# MAX-M8Q_GPS_FeatherWing.net
KiCad netlist of a schematic drawn in EAGLE
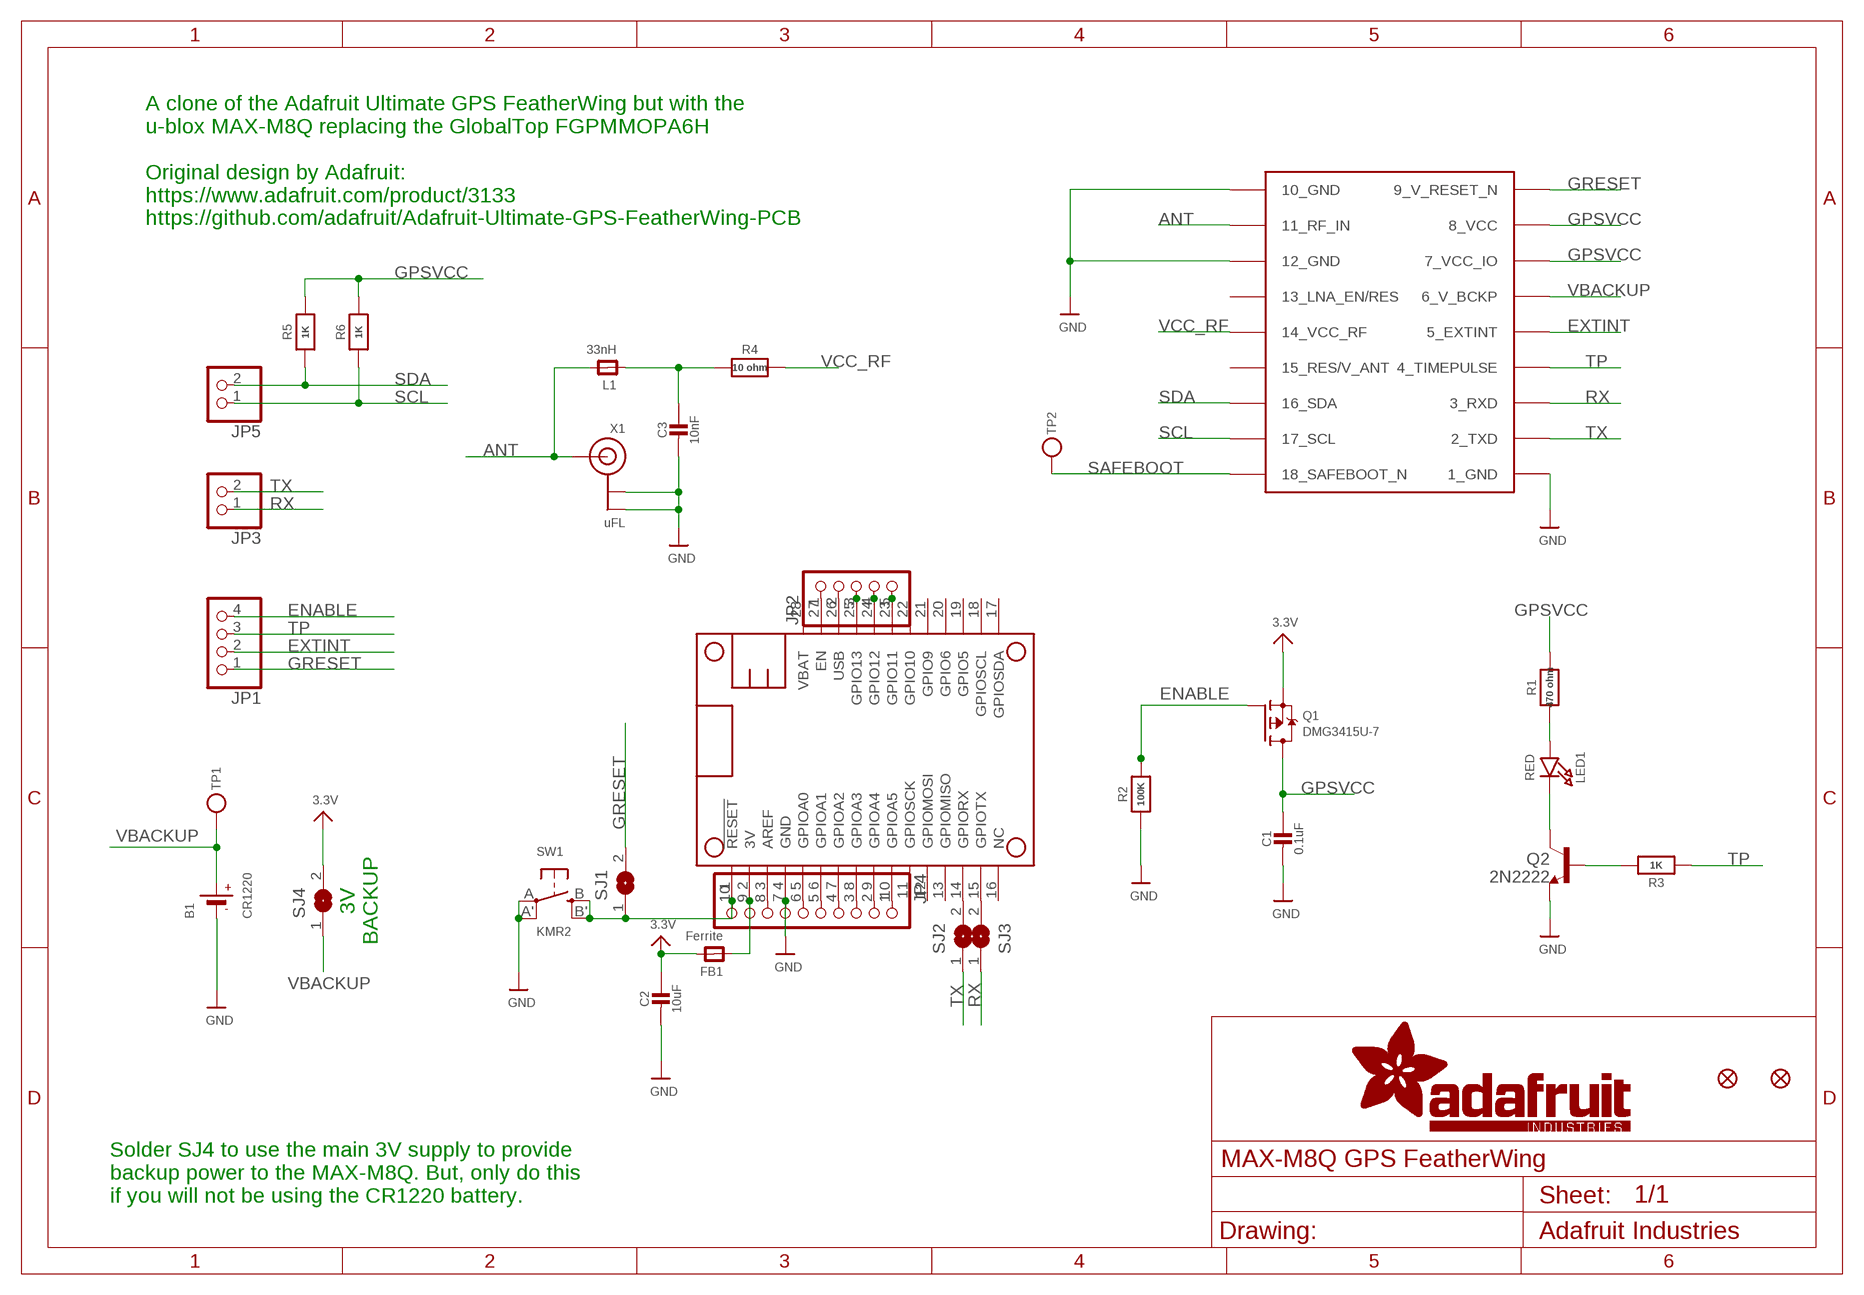
[diagram p0: schematic, sheet 1]

(export (version "E")
  (design (tool "Eeschema 10.0.6"))
  (components
    (comp (ref "B1")
      (value "CR1220")
      (footprint "eagle-import:CR1220-2")
      (libsource (lib "eagle-import") (part "BATTERYCR1220_2"))
    )
    (comp (ref "C1")
      (value "0.1uF")
      (footprint "eagle-import:0805-NO")
      (libsource (lib "eagle-import") (part "CAP_CERAMIC0805-NOOUTLINE"))
    )
    (comp (ref "C2")
      (value "10uF")
      (footprint "eagle-import:0805-NO")
      (libsource (lib "eagle-import") (part "CAP_CERAMIC0805-NOOUTLINE"))
    )
    (comp (ref "C3")
      (value "10nF")
      (footprint "eagle-import:0805-NO")
      (libsource (lib "eagle-import") (part "CAP_CERAMIC0805-NOOUTLINE"))
    )
    (comp (ref "FB1")
      (value "Ferrite")
      (footprint "eagle-import:0805-NO")
      (libsource (lib "eagle-import") (part "FERRITE-0805NO"))
    )
    (comp (ref "FID1")
      (value "FIDUCIAL\"\"")
      (footprint "eagle-import:FIDUCIAL_1MM")
      (libsource (lib "eagle-import") (part "FIDUCIAL{dblquote}{dblquote}"))
    )
    (comp (ref "FID2")
      (value "FIDUCIAL\"\"")
      (footprint "eagle-import:FIDUCIAL_1MM")
      (libsource (lib "eagle-import") (part "FIDUCIAL{dblquote}{dblquote}"))
    )
    (comp (ref "JP1")
      (value "HEADER-1X4ROUND")
      (footprint "eagle-import:1X04_ROUND")
      (libsource (lib "eagle-import") (part "HEADER-1X4ROUND"))
    )
    (comp (ref "JP2")
      (value "HEADER-1X570MIL")
      (footprint "eagle-import:1X05_ROUND_70")
      (libsource (lib "eagle-import") (part "HEADER-1X570MIL"))
    )
    (comp (ref "JP3")
      (value "HEADER-1X2ROUND")
      (footprint "eagle-import:1X02_ROUND")
      (libsource (lib "eagle-import") (part "HEADER-1X2ROUND"))
    )
    (comp (ref "JP4")
      (value "HEADER-1X10ROUND")
      (footprint "eagle-import:1X10_ROUND")
      (libsource (lib "eagle-import") (part "HEADER-1X10ROUND"))
    )
    (comp (ref "JP5")
      (value "HEADER-1X2ROUND")
      (footprint "eagle-import:1X02_ROUND")
      (libsource (lib "eagle-import") (part "HEADER-1X2ROUND"))
    )
    (comp (ref "L1")
      (value "33nH")
      (footprint "eagle-import:0805-NO")
      (libsource (lib "eagle-import") (part "FERRITE-0805NO"))
    )
    (comp (ref "LED1")
      (value "RED")
      (footprint "eagle-import:CHIPLED_0805_NOOUTLINE")
      (libsource (lib "eagle-import") (part "LED0805_NOOUTLINE"))
    )
    (comp (ref "MS1")
      (value "FEATHERWING")
      (footprint "eagle-import:FEATHERWING")
      (libsource (lib "eagle-import") (part "FEATHERWING"))
    )
    (comp (ref "Q1")
      (value "DMG3415U-7")
      (footprint "eagle-import:SOT23-WIDE")
      (libsource (lib "eagle-import") (part "MOSFET-PWIDE"))
    )
    (comp (ref "Q2")
      (value "2N2222")
      (footprint "eagle-import:SOT23-BEC")
      (libsource (lib "eagle-import") (part "-NPN-SOT23-BECMMBT2222ALT1"))
    )
    (comp (ref "R1")
      (value "470 ohm")
      (footprint "eagle-import:0805-NO")
      (libsource (lib "eagle-import") (part "RESISTOR0805_NOOUTLINE"))
    )
    (comp (ref "R2")
      (value "100K")
      (footprint "eagle-import:0805-NO")
      (libsource (lib "eagle-import") (part "RESISTOR0805_NOOUTLINE"))
    )
    (comp (ref "R3")
      (value "1K")
      (footprint "eagle-import:0805-NO")
      (libsource (lib "eagle-import") (part "RESISTOR0805_NOOUTLINE"))
    )
    (comp (ref "R4")
      (value "10 ohm")
      (footprint "eagle-import:0805-NO")
      (libsource (lib "eagle-import") (part "RESISTOR0805_NOOUTLINE"))
    )
    (comp (ref "R5")
      (value "1K")
      (footprint "eagle-import:0805-NO")
      (libsource (lib "eagle-import") (part "RESISTOR0805_NOOUTLINE"))
    )
    (comp (ref "R6")
      (value "1K")
      (footprint "eagle-import:0805-NO")
      (libsource (lib "eagle-import") (part "RESISTOR0805_NOOUTLINE"))
    )
    (comp (ref "SJ1")
      (value "SOLDERJUMPER")
      (footprint "eagle-import:SOLDERJUMPER_ARROW_NOPASTE")
      (libsource (lib "eagle-import") (part "SOLDERJUMPER"))
    )
    (comp (ref "SJ2")
      (value "SOLDERJUMPERCLOSED")
      (footprint "eagle-import:SOLDERJUMPER_CLOSEDWIRE")
      (libsource (lib "eagle-import") (part "SOLDERJUMPERCLOSED"))
    )
    (comp (ref "SJ3")
      (value "SOLDERJUMPERCLOSED")
      (footprint "eagle-import:SOLDERJUMPER_CLOSEDWIRE")
      (libsource (lib "eagle-import") (part "SOLDERJUMPERCLOSED"))
    )
    (comp (ref "SJ4")
      (value "SOLDERJUMPER")
      (footprint "eagle-import:SOLDERJUMPER_ARROW_NOPASTE")
      (libsource (lib "eagle-import") (part "SOLDERJUMPER"))
    )
    (comp (ref "SW1")
      (value "KMR2")
      (footprint "eagle-import:BTN_KMR2_4.6X2.8")
      (libsource (lib "eagle-import") (part "SWITCH_TACT_SMT4.6X2.8"))
    )
    (comp (ref "TP1")
      (value "TESTPOINTROUND1.5MM")
      (footprint "eagle-import:TESTPOINT_ROUND_1.5MM")
      (libsource (lib "eagle-import") (part "TESTPOINTROUND1.5MM"))
    )
    (comp (ref "TP2")
      (value "TESTPOINTROUND1.5MM")
      (footprint "eagle-import:TESTPOINT_ROUND_1.5MM")
      (libsource (lib "eagle-import") (part "TESTPOINTROUND1.5MM"))
    )
    (comp (ref "U1")
      (value "MAX-M8")
      (footprint "eagle-import:MAX-M8")
      (libsource (lib "eagle-import") (part "MAX-M8"))
    )
    (comp (ref "X1")
      (value "uFL")
      (footprint "eagle-import:U.FL")
      (libsource (lib "eagle-import") (part "ANTENNA_U.FL"))
    )
  )
  (nets
    (net (code "1") (name "/ANT") (class "Default")
      (node (ref "L1") (pin "2") (pinfunction "P$2_2") (pintype "passive"))
      (node (ref "U1") (pin "11_RF_IN") (pinfunction "11_RF_IN_11_RF_IN") (pintype "bidirectional"))
      (node (ref "X1") (pin "3") (pinfunction "SIGNAL_3") (pintype "passive"))
    )
    (net (code "2") (name "/ENABLE") (class "Default")
      (node (ref "JP1") (pin "4") (pinfunction "4_4") (pintype "passive"))
      (node (ref "Q1") (pin "1") (pinfunction "G_1") (pintype "passive"))
      (node (ref "R2") (pin "2") (pinfunction "2_2") (pintype "passive"))
    )
    (net (code "3") (name "/EXTINT") (class "Default")
      (node (ref "JP1") (pin "2") (pinfunction "2_2") (pintype "passive"))
      (node (ref "U1") (pin "5_EXTINT") (pinfunction "5_EXTINT_5_EXTINT") (pintype "bidirectional"))
    )
    (net (code "4") (name "/GPSVCC") (class "Default")
      (node (ref "C1") (pin "1") (pinfunction "1_1") (pintype "passive"))
      (node (ref "Q1") (pin "3") (pinfunction "D_3") (pintype "passive"))
      (node (ref "R1") (pin "2") (pinfunction "2_2") (pintype "passive"))
      (node (ref "R5") (pin "2") (pinfunction "2_2") (pintype "passive"))
      (node (ref "R6") (pin "2") (pinfunction "2_2") (pintype "passive"))
      (node (ref "U1") (pin "7_VCC_IO") (pinfunction "7_VCC_IO_7_VCC_IO") (pintype "power_in"))
      (node (ref "U1") (pin "8_VCC") (pinfunction "8_VCC_8_VCC") (pintype "power_in"))
    )
    (net (code "5") (name "/GRESET") (class "Default")
      (node (ref "JP1") (pin "1") (pinfunction "1_1") (pintype "passive"))
      (node (ref "SJ1") (pin "2") (pinfunction "2_2") (pintype "passive"))
      (node (ref "U1") (pin "9_RESET_N") (pinfunction "9_V_RESET_N_9_RESET_N") (pintype "power_in"))
    )
    (net (code "6") (name "/RX") (class "Default")
      (node (ref "JP3") (pin "1") (pinfunction "1_1") (pintype "passive"))
      (node (ref "SJ3") (pin "1") (pinfunction "1_1") (pintype "passive"))
      (node (ref "U1") (pin "3_RXD") (pinfunction "3_RXD_3_RXD") (pintype "bidirectional"))
    )
    (net (code "7") (name "/SAFEBOOT") (class "Default")
      (node (ref "TP2") (pin "P$1") (pinfunction "P$1_P$1") (pintype "bidirectional"))
      (node (ref "U1") (pin "18_SAFEBOOT_N") (pinfunction "18_SAFEBOOT_N_18_SAFEBOOT_N") (pintype "bidirectional"))
    )
    (net (code "8") (name "/SCL") (class "Default")
      (node (ref "JP5") (pin "1") (pinfunction "1_1") (pintype "passive"))
      (node (ref "R6") (pin "1") (pinfunction "1_1") (pintype "passive"))
      (node (ref "U1") (pin "17_SCL") (pinfunction "17_SCL_17_SCL") (pintype "bidirectional"))
    )
    (net (code "9") (name "/SDA") (class "Default")
      (node (ref "JP5") (pin "2") (pinfunction "2_2") (pintype "passive"))
      (node (ref "R5") (pin "1") (pinfunction "1_1") (pintype "passive"))
      (node (ref "U1") (pin "16_SDA") (pinfunction "16_SDA_16_SDA") (pintype "bidirectional"))
    )
    (net (code "10") (name "/TP") (class "Default")
      (node (ref "JP1") (pin "3") (pinfunction "3_3") (pintype "passive"))
      (node (ref "R3") (pin "1") (pinfunction "1_1") (pintype "passive"))
      (node (ref "U1") (pin "4_TIMEPULSE") (pinfunction "4_TIMEPULSE_4_TIMEPULSE") (pintype "bidirectional"))
    )
    (net (code "11") (name "/TX") (class "Default")
      (node (ref "JP3") (pin "2") (pinfunction "2_2") (pintype "passive"))
      (node (ref "SJ2") (pin "1") (pinfunction "1_1") (pintype "passive"))
      (node (ref "U1") (pin "2_TXD") (pinfunction "2_TXD_2_TXD") (pintype "bidirectional"))
    )
    (net (code "12") (name "/VBACKUP") (class "Default")
      (node (ref "B1") (pin "+") (pinfunction "+_+") (pintype "passive"))
      (node (ref "SJ4") (pin "1") (pinfunction "1_1") (pintype "passive"))
      (node (ref "TP1") (pin "P$1") (pinfunction "P$1_P$1") (pintype "bidirectional"))
      (node (ref "U1") (pin "6_V_BCKP") (pinfunction "6_V_BCKP_6_V_BCKP") (pintype "bidirectional"))
    )
    (net (code "13") (name "/VBAT") (class "Default")
      (node (ref "MS1") (pin "28") (pinfunction "VBAT_28") (pintype "power_in"))
    )
    (net (code "14") (name "/VCC_RF") (class "Default")
      (node (ref "R4") (pin "2") (pinfunction "2_2") (pintype "passive"))
      (node (ref "U1") (pin "14_VCC_RF") (pinfunction "14_VCC_RF_14_VCC_RF") (pintype "bidirectional"))
    )
    (net (code "15") (name "3.3V") (class "Default")
      (node (ref "C2") (pin "1") (pinfunction "1_1") (pintype "passive"))
      (node (ref "FB1") (pin "2") (pinfunction "P$2_2") (pintype "passive"))
      (node (ref "Q1") (pin "2") (pinfunction "S_2") (pintype "passive"))
      (node (ref "SJ4") (pin "2") (pinfunction "2_2") (pintype "passive"))
    )
    (net (code "16") (name "GND") (class "Default")
      (node (ref "B1") (pin "-") (pinfunction "-_-") (pintype "passive"))
      (node (ref "C1") (pin "2") (pinfunction "2_2") (pintype "passive"))
      (node (ref "C2") (pin "2") (pinfunction "2_2") (pintype "passive"))
      (node (ref "C3") (pin "2") (pinfunction "2_2") (pintype "passive"))
      (node (ref "JP4") (pin "7") (pinfunction "7_7") (pintype "passive"))
      (node (ref "MS1") (pin "4") (pinfunction "GND_4") (pintype "power_in"))
      (node (ref "Q2") (pin "E") (pinfunction "E_E") (pintype "passive"))
      (node (ref "R2") (pin "1") (pinfunction "1_1") (pintype "passive"))
      (node (ref "SW1") (pin "A") (pinfunction "P_A") (pintype "passive"))
      (node (ref "SW1") (pin "A'") (pinfunction "P1_A'") (pintype "passive"))
      (node (ref "U1") (pin "10_GND") (pinfunction "10_GND_10_GND") (pintype "power_in"))
      (node (ref "U1") (pin "12_GND") (pinfunction "12_GND_12_GND") (pintype "power_in"))
      (node (ref "U1") (pin "1_GND") (pinfunction "1_GND_1_GND") (pintype "power_in"))
      (node (ref "X1") (pin "1") (pinfunction "GND_1") (pintype "passive"))
      (node (ref "X1") (pin "2") (pinfunction "GND_2") (pintype "passive"))
    )
    (net (code "17") (name "Net-(FB1-P$1)") (class "Default")
      (node (ref "FB1") (pin "1") (pinfunction "P$1_1") (pintype "passive"))
      (node (ref "JP4") (pin "9") (pinfunction "9_9") (pintype "passive"))
      (node (ref "MS1") (pin "2") (pinfunction "3V_2") (pintype "power_in"))
    )
    (net (code "18") (name "Net-(L1-P$1)") (class "Default")
      (node (ref "C3") (pin "1") (pinfunction "1_1") (pintype "passive"))
      (node (ref "L1") (pin "1") (pinfunction "P$1_1") (pintype "passive"))
      (node (ref "R4") (pin "1") (pinfunction "1_1") (pintype "passive"))
    )
    (net (code "19") (name "Net-(LED1-PadA)") (class "Default")
      (node (ref "LED1") (pin "A") (pinfunction "A_A") (pintype "passive"))
      (node (ref "R1") (pin "1") (pinfunction "1_1") (pintype "passive"))
    )
    (net (code "20") (name "Net-(LED1-PadC)") (class "Default")
      (node (ref "LED1") (pin "C") (pinfunction "C_C") (pintype "passive"))
      (node (ref "Q2") (pin "C") (pinfunction "C_C") (pintype "passive"))
    )
    (net (code "21") (name "Net-(MS1-AREF)") (class "Default")
      (node (ref "JP4") (pin "8") (pinfunction "8_8") (pintype "passive"))
      (node (ref "MS1") (pin "3") (pinfunction "AREF_3") (pintype "passive"))
    )
    (net (code "22") (name "Net-(MS1-EN)") (class "Default")
      (node (ref "JP2") (pin "1") (pinfunction "1_1") (pintype "passive"))
      (node (ref "MS1") (pin "27") (pinfunction "EN_27") (pintype "passive"))
    )
    (net (code "23") (name "Net-(MS1-GPIO11)") (class "Default")
      (node (ref "JP2") (pin "5") (pinfunction "5_5") (pintype "passive"))
      (node (ref "MS1") (pin "23") (pinfunction "GPIO11_23") (pintype "bidirectional"))
    )
    (net (code "24") (name "Net-(MS1-GPIO12)") (class "Default")
      (node (ref "JP2") (pin "4") (pinfunction "4_4") (pintype "passive"))
      (node (ref "MS1") (pin "24") (pinfunction "GPIO12_24") (pintype "bidirectional"))
    )
    (net (code "25") (name "Net-(MS1-GPIO13)") (class "Default")
      (node (ref "JP2") (pin "3") (pinfunction "3_3") (pintype "passive"))
      (node (ref "MS1") (pin "25") (pinfunction "GPIO13_25") (pintype "bidirectional"))
    )
    (net (code "26") (name "Net-(MS1-GPIOA0)") (class "Default")
      (node (ref "JP4") (pin "6") (pinfunction "6_6") (pintype "passive"))
      (node (ref "MS1") (pin "5") (pinfunction "GPIOA0_5") (pintype "bidirectional"))
    )
    (net (code "27") (name "Net-(MS1-GPIOA1)") (class "Default")
      (node (ref "JP4") (pin "5") (pinfunction "5_5") (pintype "passive"))
      (node (ref "MS1") (pin "6") (pinfunction "GPIOA1_6") (pintype "bidirectional"))
    )
    (net (code "28") (name "Net-(MS1-GPIOA2)") (class "Default")
      (node (ref "JP4") (pin "4") (pinfunction "4_4") (pintype "passive"))
      (node (ref "MS1") (pin "7") (pinfunction "GPIOA2_7") (pintype "bidirectional"))
    )
    (net (code "29") (name "Net-(MS1-GPIOA3)") (class "Default")
      (node (ref "JP4") (pin "3") (pinfunction "3_3") (pintype "passive"))
      (node (ref "MS1") (pin "8") (pinfunction "GPIOA3_8") (pintype "bidirectional"))
    )
    (net (code "30") (name "Net-(MS1-GPIOA4)") (class "Default")
      (node (ref "JP4") (pin "2") (pinfunction "2_2") (pintype "passive"))
      (node (ref "MS1") (pin "9") (pinfunction "GPIOA4_9") (pintype "bidirectional"))
    )
    (net (code "31") (name "Net-(MS1-GPIOA5)") (class "Default")
      (node (ref "JP4") (pin "1") (pinfunction "1_1") (pintype "passive"))
      (node (ref "MS1") (pin "10") (pinfunction "GPIOA5_10") (pintype "bidirectional"))
    )
    (net (code "32") (name "Net-(MS1-GPIORX)") (class "Default")
      (node (ref "MS1") (pin "14") (pinfunction "GPIORX_14") (pintype "bidirectional"))
      (node (ref "SJ2") (pin "2") (pinfunction "2_2") (pintype "passive"))
    )
    (net (code "33") (name "Net-(MS1-GPIOTX)") (class "Default")
      (node (ref "MS1") (pin "15") (pinfunction "GPIOTX_15") (pintype "bidirectional"))
      (node (ref "SJ3") (pin "2") (pinfunction "2_2") (pintype "passive"))
    )
    (net (code "34") (name "Net-(MS1-USB)") (class "Default")
      (node (ref "JP2") (pin "2") (pinfunction "2_2") (pintype "passive"))
      (node (ref "MS1") (pin "26") (pinfunction "USB_26") (pintype "power_in"))
    )
    (net (code "35") (name "Net-(MS1-~{RESET})") (class "Default")
      (node (ref "JP4") (pin "10") (pinfunction "10_10") (pintype "passive"))
      (node (ref "MS1") (pin "1") (pinfunction "~{RESET}_1") (pintype "input"))
      (node (ref "SJ1") (pin "1") (pinfunction "1_1") (pintype "passive"))
      (node (ref "SW1") (pin "B") (pinfunction "S_B") (pintype "passive"))
      (node (ref "SW1") (pin "B'") (pinfunction "S1_B'") (pintype "passive"))
    )
    (net (code "36") (name "Net-(Q2-PadB)") (class "Default")
      (node (ref "Q2") (pin "B") (pinfunction "B_B") (pintype "passive"))
      (node (ref "R3") (pin "2") (pinfunction "2_2") (pintype "passive"))
    )
    (net (code "37") (name "unconnected-(MS1-GPIO5-Pad19)") (class "Default")
      (node (ref "MS1") (pin "19") (pinfunction "GPIO5_19") (pintype "bidirectional"))
    )
    (net (code "38") (name "unconnected-(MS1-GPIO6-Pad20)") (class "Default")
      (node (ref "MS1") (pin "20") (pinfunction "GPIO6_20") (pintype "bidirectional"))
    )
    (net (code "39") (name "unconnected-(MS1-GPIO9-Pad21)") (class "Default")
      (node (ref "MS1") (pin "21") (pinfunction "GPIO9_21") (pintype "bidirectional"))
    )
    (net (code "40") (name "unconnected-(MS1-GPIO10-Pad22)") (class "Default")
      (node (ref "MS1") (pin "22") (pinfunction "GPIO10_22") (pintype "bidirectional"))
    )
    (net (code "41") (name "unconnected-(MS1-GPIOMISO-Pad13)") (class "Default")
      (node (ref "MS1") (pin "13") (pinfunction "GPIOMISO_13") (pintype "bidirectional"))
    )
    (net (code "42") (name "unconnected-(MS1-GPIOMOSI-Pad12)") (class "Default")
      (node (ref "MS1") (pin "12") (pinfunction "GPIOMOSI_12") (pintype "bidirectional"))
    )
    (net (code "43") (name "unconnected-(MS1-GPIOSCK-Pad11)") (class "Default")
      (node (ref "MS1") (pin "11") (pinfunction "GPIOSCK_11") (pintype "bidirectional"))
    )
    (net (code "44") (name "unconnected-(MS1-GPIOSCL-Pad18)") (class "Default")
      (node (ref "MS1") (pin "18") (pinfunction "GPIOSCL_18") (pintype "bidirectional"))
    )
    (net (code "45") (name "unconnected-(MS1-GPIOSDA-Pad17)") (class "Default")
      (node (ref "MS1") (pin "17") (pinfunction "GPIOSDA_17") (pintype "bidirectional"))
    )
    (net (code "46") (name "unconnected-(MS1-NC-Pad16)") (class "Default")
      (node (ref "MS1") (pin "16") (pinfunction "NC_16") (pintype "passive"))
    )
    (net (code "47") (name "unconnected-(U1-13_LNA_EN{slash}RES-Pad13_LNA_EN)") (class "Default")
      (node (ref "U1") (pin "13_LNA_EN") (pinfunction "13_LNA_EN/RES_13_LNA_EN") (pintype "bidirectional"))
    )
    (net (code "48") (name "unconnected-(U1-15_RES{slash}V_ANT-Pad15_V_ANT{slash}RESERVED)") (class "Default")
      (node (ref "U1") (pin "15_V_ANT/RESERVED") (pinfunction "15_RES/V_ANT_15_V_ANT/RESERVED") (pintype "bidirectional"))
    )
  )
)
